# esp12-1-1.net
KiCad netlist of a schematic drawn in EAGLE
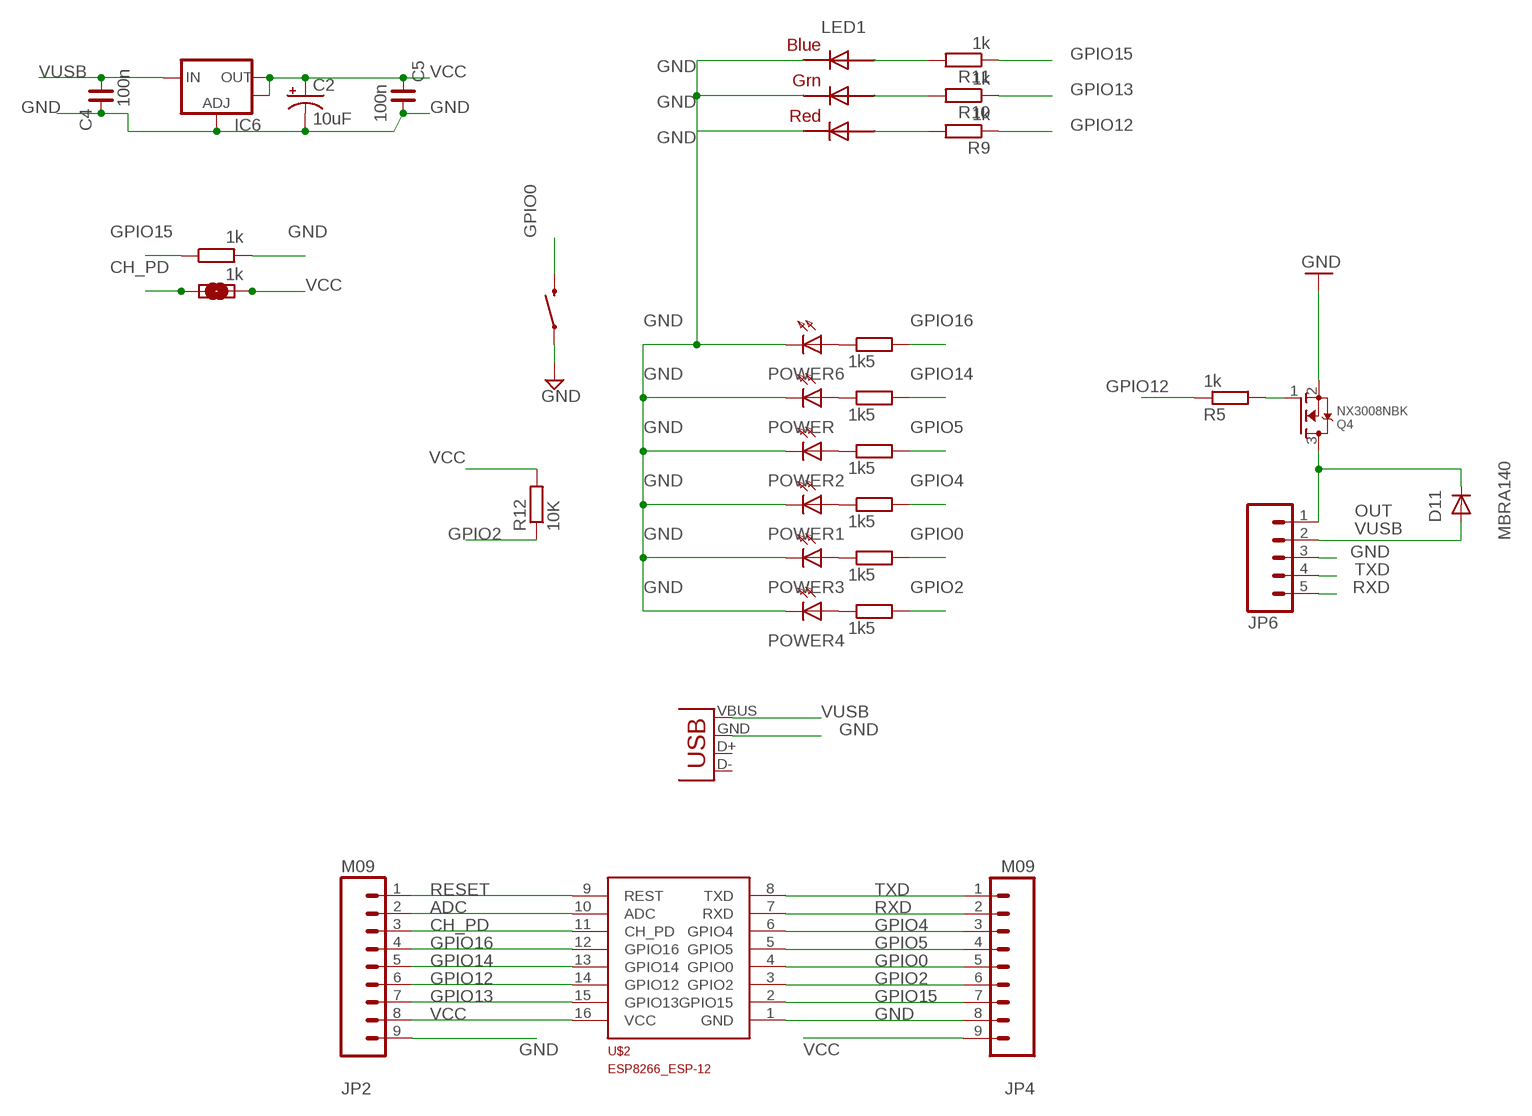
[diagram p0: schematic, sheet 1]

(export (version "E")
  (design (tool "Eeschema 10.0.6"))
  (components
    (comp (ref "C2")
      (value "10uF")
      (footprint "eagle-import:EIA3216")
      (libsource (lib "eagle-import") (part "CAP_POL1206"))
    )
    (comp (ref "C4")
      (value "100n")
      (footprint "eagle-import:C0603")
      (libsource (lib "eagle-import") (part "C_0603"))
    )
    (comp (ref "C5")
      (value "100n")
      (footprint "eagle-import:C0603")
      (libsource (lib "eagle-import") (part "C_0603"))
    )
    (comp (ref "D11")
      (value "MBRA140")
      (footprint "eagle-import:SOD-323")
      (libsource (lib "eagle-import") (part "DIODESOD"))
    )
    (comp (ref "IC6")
      (value "V_REG_LM1117SOT223")
      (footprint "eagle-import:SOT223")
      (libsource (lib "eagle-import") (part "V_REG_LM1117SOT223"))
    )
    (comp (ref "JP2")
      (value "M09")
      (footprint "eagle-import:1X09")
      (libsource (lib "eagle-import") (part "M09"))
    )
    (comp (ref "JP4")
      (value "M09")
      (footprint "eagle-import:1X09")
      (libsource (lib "eagle-import") (part "M09"))
    )
    (comp (ref "JP6")
      (value "M05NO_SILK")
      (footprint "eagle-import:1X05_NO_SILK")
      (libsource (lib "eagle-import") (part "M05NO_SILK"))
    )
    (comp (ref "LED1")
      (value "RGBLED5050")
      (footprint "eagle-import:RGBLED5050")
      (libsource (lib "eagle-import") (part "RGBLED5050"))
    )
    (comp (ref "POWER")
      (value "NA")
      (footprint "eagle-import:LED-0603")
      (libsource (lib "eagle-import") (part "LED0603DWS"))
    )
    (comp (ref "POWER1")
      (value "NA")
      (footprint "eagle-import:LED-0603")
      (libsource (lib "eagle-import") (part "LED0603DWS"))
    )
    (comp (ref "POWER2")
      (value "NA")
      (footprint "eagle-import:LED-0603")
      (libsource (lib "eagle-import") (part "LED0603DWS"))
    )
    (comp (ref "POWER3")
      (value "NA")
      (footprint "eagle-import:LED-0603")
      (libsource (lib "eagle-import") (part "LED0603DWS"))
    )
    (comp (ref "POWER4")
      (value "NA")
      (footprint "eagle-import:LED-0603")
      (libsource (lib "eagle-import") (part "LED0603DWS"))
    )
    (comp (ref "POWER6")
      (value "NA")
      (footprint "eagle-import:LED-0603")
      (libsource (lib "eagle-import") (part "LED0603DWS"))
    )
    (comp (ref "PWR2")
      (value "SOLDERJUMPERNO")
      (footprint "eagle-import:SJ_2S-NO")
      (libsource (lib "eagle-import") (part "SOLDERJUMPERNO"))
    )
    (comp (ref "Q4")
      (value "NX3008NBK")
      (footprint "eagle-import:SOT23-WIDE")
      (libsource (lib "eagle-import") (part "MOSFET-NWIDE"))
    )
    (comp (ref "R1")
      (value "1k5")
      (footprint "eagle-import:R0603")
      (libsource (lib "eagle-import") (part "resistor_R-EU_R0603"))
    )
    (comp (ref "R2")
      (value "1k5")
      (footprint "eagle-import:R0603")
      (libsource (lib "eagle-import") (part "resistor_R-EU_R0603"))
    )
    (comp (ref "R3")
      (value "1k5")
      (footprint "eagle-import:R0603")
      (libsource (lib "eagle-import") (part "resistor_R-EU_R0603"))
    )
    (comp (ref "R4")
      (value "1k5")
      (footprint "eagle-import:R0603")
      (libsource (lib "eagle-import") (part "resistor_R-EU_R0603"))
    )
    (comp (ref "R5")
      (value "1k")
      (footprint "eagle-import:R0603")
      (libsource (lib "eagle-import") (part "resistor_R-EU_R0603"))
    )
    (comp (ref "R6")
      (value "1k5")
      (footprint "eagle-import:R0603")
      (libsource (lib "eagle-import") (part "resistor_R-EU_R0603"))
    )
    (comp (ref "R7")
      (value "1k")
      (footprint "eagle-import:R0603")
      (libsource (lib "eagle-import") (part "resistor_R-EU_R0603"))
    )
    (comp (ref "R8")
      (value "1k")
      (footprint "eagle-import:R0603")
      (libsource (lib "eagle-import") (part "resistor_R-EU_R0603"))
    )
    (comp (ref "R9")
      (value "1k")
      (footprint "eagle-import:R0603")
      (libsource (lib "eagle-import") (part "resistor_R-EU_R0603"))
    )
    (comp (ref "R10")
      (value "1k")
      (footprint "eagle-import:R0603")
      (libsource (lib "eagle-import") (part "resistor_R-EU_R0603"))
    )
    (comp (ref "R11")
      (value "1k")
      (footprint "eagle-import:R0603")
      (libsource (lib "eagle-import") (part "resistor_R-EU_R0603"))
    )
    (comp (ref "R12")
      (value "10K")
      (footprint "eagle-import:R0603")
      (libsource (lib "eagle-import") (part "R-EU_R0603"))
    )
    (comp (ref "R13")
      (value "1k5")
      (footprint "eagle-import:R0603")
      (libsource (lib "eagle-import") (part "resistor_R-EU_R0603"))
    )
    (comp (ref "RESET1")
      (value "SWITCH-MOMENTARY-2-SMD-1101NE")
      (footprint "eagle-import:TACTILE-SWITCH-1101NE")
      (libsource (lib "eagle-import") (part "SWITCH-MOMENTARY-2-SMD-1101NE"))
    )
    (comp (ref "U$2")
      (value "ESP8266_ESP-12")
      (footprint "eagle-import:ESP8266-ESP12")
      (libsource (lib "eagle-import") (part "ESP8266_ESP-12"))
    )
    (comp (ref "X3")
      (value "USB-A-H")
      (footprint "eagle-import:USB-A-H")
      (libsource (lib "eagle-import") (part "USB-A-H"))
    )
  )
  (nets
    (net (code "1") (name "/ADC") (class "Default")
      (node (ref "JP2") (pin "2") (pinfunction "2_2") (pintype "passive"))
      (node (ref "U$2") (pin "10") (pinfunction "ADC_10") (pintype "bidirectional"))
    )
    (net (code "2") (name "/CH_PD") (class "Default")
      (node (ref "JP2") (pin "3") (pinfunction "3_3") (pintype "passive"))
      (node (ref "PWR2") (pin "1") (pinfunction "1_1") (pintype "passive"))
      (node (ref "R8") (pin "2") (pinfunction "2_2") (pintype "passive"))
      (node (ref "U$2") (pin "11") (pinfunction "CH_PD_11") (pintype "bidirectional"))
    )
    (net (code "3") (name "/GPIO0") (class "Default")
      (node (ref "JP4") (pin "5") (pinfunction "5_5") (pintype "passive"))
      (node (ref "R3") (pin "2") (pinfunction "2_2") (pintype "passive"))
      (node (ref "RESET1") (pin "P$2") (pinfunction "2_P$2") (pintype "passive"))
      (node (ref "U$2") (pin "4") (pinfunction "GPIO0_4") (pintype "bidirectional"))
    )
    (net (code "4") (name "/GPIO2") (class "Default")
      (node (ref "JP4") (pin "6") (pinfunction "6_6") (pintype "passive"))
      (node (ref "R12") (pin "1") (pinfunction "1_1") (pintype "passive"))
      (node (ref "R4") (pin "2") (pinfunction "2_2") (pintype "passive"))
      (node (ref "U$2") (pin "3") (pinfunction "GPIO2_3") (pintype "bidirectional"))
    )
    (net (code "5") (name "/GPIO4") (class "Default")
      (node (ref "JP4") (pin "3") (pinfunction "3_3") (pintype "passive"))
      (node (ref "R1") (pin "2") (pinfunction "2_2") (pintype "passive"))
      (node (ref "U$2") (pin "6") (pinfunction "GPIO4_6") (pintype "bidirectional"))
    )
    (net (code "6") (name "/GPIO5") (class "Default")
      (node (ref "JP4") (pin "4") (pinfunction "4_4") (pintype "passive"))
      (node (ref "R2") (pin "2") (pinfunction "2_2") (pintype "passive"))
      (node (ref "U$2") (pin "5") (pinfunction "GPIO5_5") (pintype "bidirectional"))
    )
    (net (code "7") (name "/GPIO12") (class "Default")
      (node (ref "JP2") (pin "6") (pinfunction "6_6") (pintype "passive"))
      (node (ref "R5") (pin "1") (pinfunction "1_1") (pintype "passive"))
      (node (ref "R9") (pin "1") (pinfunction "1_1") (pintype "passive"))
      (node (ref "U$2") (pin "14") (pinfunction "GPIO12_14") (pintype "bidirectional"))
    )
    (net (code "8") (name "/GPIO13") (class "Default")
      (node (ref "JP2") (pin "7") (pinfunction "7_7") (pintype "passive"))
      (node (ref "R10") (pin "1") (pinfunction "1_1") (pintype "passive"))
      (node (ref "U$2") (pin "15") (pinfunction "GPIO13_15") (pintype "bidirectional"))
    )
    (net (code "9") (name "/GPIO14") (class "Default")
      (node (ref "JP2") (pin "5") (pinfunction "5_5") (pintype "passive"))
      (node (ref "R13") (pin "2") (pinfunction "2_2") (pintype "passive"))
      (node (ref "U$2") (pin "13") (pinfunction "GPIO14_13") (pintype "bidirectional"))
    )
    (net (code "10") (name "/GPIO15") (class "Default")
      (node (ref "JP4") (pin "7") (pinfunction "7_7") (pintype "passive"))
      (node (ref "R11") (pin "1") (pinfunction "1_1") (pintype "passive"))
      (node (ref "R7") (pin "1") (pinfunction "1_1") (pintype "passive"))
      (node (ref "U$2") (pin "2") (pinfunction "GPIO15_2") (pintype "bidirectional"))
    )
    (net (code "11") (name "/GPIO16") (class "Default")
      (node (ref "JP2") (pin "4") (pinfunction "4_4") (pintype "passive"))
      (node (ref "R6") (pin "2") (pinfunction "2_2") (pintype "passive"))
      (node (ref "U$2") (pin "12") (pinfunction "GPIO16_12") (pintype "bidirectional"))
    )
    (net (code "12") (name "/OUT") (class "Default")
      (node (ref "D11") (pin "1") (pinfunction "C_1") (pintype "passive"))
      (node (ref "JP6") (pin "1") (pinfunction "1_1") (pintype "passive"))
      (node (ref "Q4") (pin "3") (pinfunction "D_3") (pintype "bidirectional"))
    )
    (net (code "13") (name "/RESET") (class "Default")
      (node (ref "JP2") (pin "1") (pinfunction "1_1") (pintype "passive"))
      (node (ref "U$2") (pin "9") (pinfunction "REST_9") (pintype "bidirectional"))
    )
    (net (code "14") (name "/RXD") (class "Default")
      (node (ref "JP4") (pin "2") (pinfunction "2_2") (pintype "passive"))
      (node (ref "JP6") (pin "5") (pinfunction "5_5") (pintype "passive"))
      (node (ref "U$2") (pin "7") (pinfunction "RXD_7") (pintype "bidirectional"))
    )
    (net (code "15") (name "/TXD") (class "Default")
      (node (ref "JP4") (pin "1") (pinfunction "1_1") (pintype "passive"))
      (node (ref "JP6") (pin "4") (pinfunction "4_4") (pintype "passive"))
      (node (ref "U$2") (pin "8") (pinfunction "TXD_8") (pintype "bidirectional"))
    )
    (net (code "16") (name "/VCC") (class "Default")
      (node (ref "C2") (pin "A") (pinfunction "+_A") (pintype "passive"))
      (node (ref "C5") (pin "2") (pinfunction "2_2") (pintype "passive"))
      (node (ref "IC6") (pin "2") (pinfunction "OUT_2") (pintype "output"))
      (node (ref "IC6") (pin "4") (pinfunction "OUT_4") (pintype "output"))
      (node (ref "JP2") (pin "8") (pinfunction "8_8") (pintype "passive"))
      (node (ref "JP4") (pin "9") (pinfunction "9_9") (pintype "passive"))
      (node (ref "PWR2") (pin "2") (pinfunction "2_2") (pintype "passive"))
      (node (ref "R12") (pin "2") (pinfunction "2_2") (pintype "passive"))
      (node (ref "R8") (pin "1") (pinfunction "1_1") (pintype "passive"))
      (node (ref "U$2") (pin "16") (pinfunction "VCC_16") (pintype "bidirectional"))
    )
    (net (code "17") (name "/VUSB") (class "Default")
      (node (ref "C4") (pin "1") (pinfunction "1_1") (pintype "passive"))
      (node (ref "D11") (pin "2") (pinfunction "A_2") (pintype "passive"))
      (node (ref "IC6") (pin "3") (pinfunction "IN_3") (pintype "input"))
      (node (ref "JP6") (pin "2") (pinfunction "2_2") (pintype "passive"))
      (node (ref "X3") (pin "VBUS") (pinfunction "GND_VBUS") (pintype "bidirectional"))
    )
    (net (code "18") (name "GND") (class "Default")
      (node (ref "C2") (pin "C") (pinfunction "-_C") (pintype "passive"))
      (node (ref "C4") (pin "2") (pinfunction "2_2") (pintype "passive"))
      (node (ref "C5") (pin "1") (pinfunction "1_1") (pintype "passive"))
      (node (ref "IC6") (pin "1") (pinfunction "ADJ_1") (pintype "input"))
      (node (ref "JP2") (pin "9") (pinfunction "9_9") (pintype "passive"))
      (node (ref "JP4") (pin "8") (pinfunction "8_8") (pintype "passive"))
      (node (ref "JP6") (pin "3") (pinfunction "3_3") (pintype "passive"))
      (node (ref "LED1") (pin "4") (pinfunction "BLUE_C_4") (pintype "bidirectional"))
      (node (ref "LED1") (pin "5") (pinfunction "RED_C_5") (pintype "bidirectional"))
      (node (ref "LED1") (pin "6") (pinfunction "GREEN_C_6") (pintype "bidirectional"))
      (node (ref "POWER") (pin "C") (pinfunction "C_C") (pintype "passive"))
      (node (ref "POWER1") (pin "C") (pinfunction "C_C") (pintype "passive"))
      (node (ref "POWER2") (pin "C") (pinfunction "C_C") (pintype "passive"))
      (node (ref "POWER3") (pin "C") (pinfunction "C_C") (pintype "passive"))
      (node (ref "POWER4") (pin "C") (pinfunction "C_C") (pintype "passive"))
      (node (ref "POWER6") (pin "C") (pinfunction "C_C") (pintype "passive"))
      (node (ref "Q4") (pin "2") (pinfunction "S_2") (pintype "bidirectional"))
      (node (ref "R7") (pin "2") (pinfunction "2_2") (pintype "passive"))
      (node (ref "RESET1") (pin "P$1") (pinfunction "1_P$1") (pintype "passive"))
      (node (ref "U$2") (pin "1") (pinfunction "GND_1") (pintype "bidirectional"))
      (node (ref "X3") (pin "GND") (pinfunction "VBUS_GND") (pintype "bidirectional"))
    )
    (net (code "19") (name "Net-(LED1-BLUE_A)") (class "Default")
      (node (ref "LED1") (pin "3") (pinfunction "BLUE_A_3") (pintype "bidirectional"))
      (node (ref "R11") (pin "2") (pinfunction "2_2") (pintype "passive"))
    )
    (net (code "20") (name "Net-(LED1-GREEN_A)") (class "Default")
      (node (ref "LED1") (pin "1") (pinfunction "GREEN_A_1") (pintype "bidirectional"))
      (node (ref "R10") (pin "2") (pinfunction "2_2") (pintype "passive"))
    )
    (net (code "21") (name "Net-(LED1-RED_A)") (class "Default")
      (node (ref "LED1") (pin "2") (pinfunction "RED_A_2") (pintype "bidirectional"))
      (node (ref "R9") (pin "2") (pinfunction "2_2") (pintype "passive"))
    )
    (net (code "22") (name "Net-(POWER-PadA)") (class "Default")
      (node (ref "POWER") (pin "A") (pinfunction "A_A") (pintype "passive"))
      (node (ref "R13") (pin "1") (pinfunction "1_1") (pintype "passive"))
    )
    (net (code "23") (name "Net-(POWER1-PadA)") (class "Default")
      (node (ref "POWER1") (pin "A") (pinfunction "A_A") (pintype "passive"))
      (node (ref "R1") (pin "1") (pinfunction "1_1") (pintype "passive"))
    )
    (net (code "24") (name "Net-(POWER2-PadA)") (class "Default")
      (node (ref "POWER2") (pin "A") (pinfunction "A_A") (pintype "passive"))
      (node (ref "R2") (pin "1") (pinfunction "1_1") (pintype "passive"))
    )
    (net (code "25") (name "Net-(POWER3-PadA)") (class "Default")
      (node (ref "POWER3") (pin "A") (pinfunction "A_A") (pintype "passive"))
      (node (ref "R3") (pin "1") (pinfunction "1_1") (pintype "passive"))
    )
    (net (code "26") (name "Net-(POWER4-PadA)") (class "Default")
      (node (ref "POWER4") (pin "A") (pinfunction "A_A") (pintype "passive"))
      (node (ref "R4") (pin "1") (pinfunction "1_1") (pintype "passive"))
    )
    (net (code "27") (name "Net-(POWER6-PadA)") (class "Default")
      (node (ref "POWER6") (pin "A") (pinfunction "A_A") (pintype "passive"))
      (node (ref "R6") (pin "1") (pinfunction "1_1") (pintype "passive"))
    )
    (net (code "28") (name "Net-(Q4-G)") (class "Default")
      (node (ref "Q4") (pin "1") (pinfunction "G_1") (pintype "bidirectional"))
      (node (ref "R5") (pin "2") (pinfunction "2_2") (pintype "passive"))
    )
    (net (code "29") (name "unconnected-(X3-D+-PadD-)") (class "Default")
      (node (ref "X3") (pin "D-") (pinfunction "D+_D-") (pintype "bidirectional"))
    )
    (net (code "30") (name "unconnected-(X3-D--PadD+)") (class "Default")
      (node (ref "X3") (pin "D+") (pinfunction "D-_D+") (pintype "bidirectional"))
    )
  )
)
